# USB2Serial_CH340G_v1_2.net
KiCad netlist of a schematic drawn in EAGLE
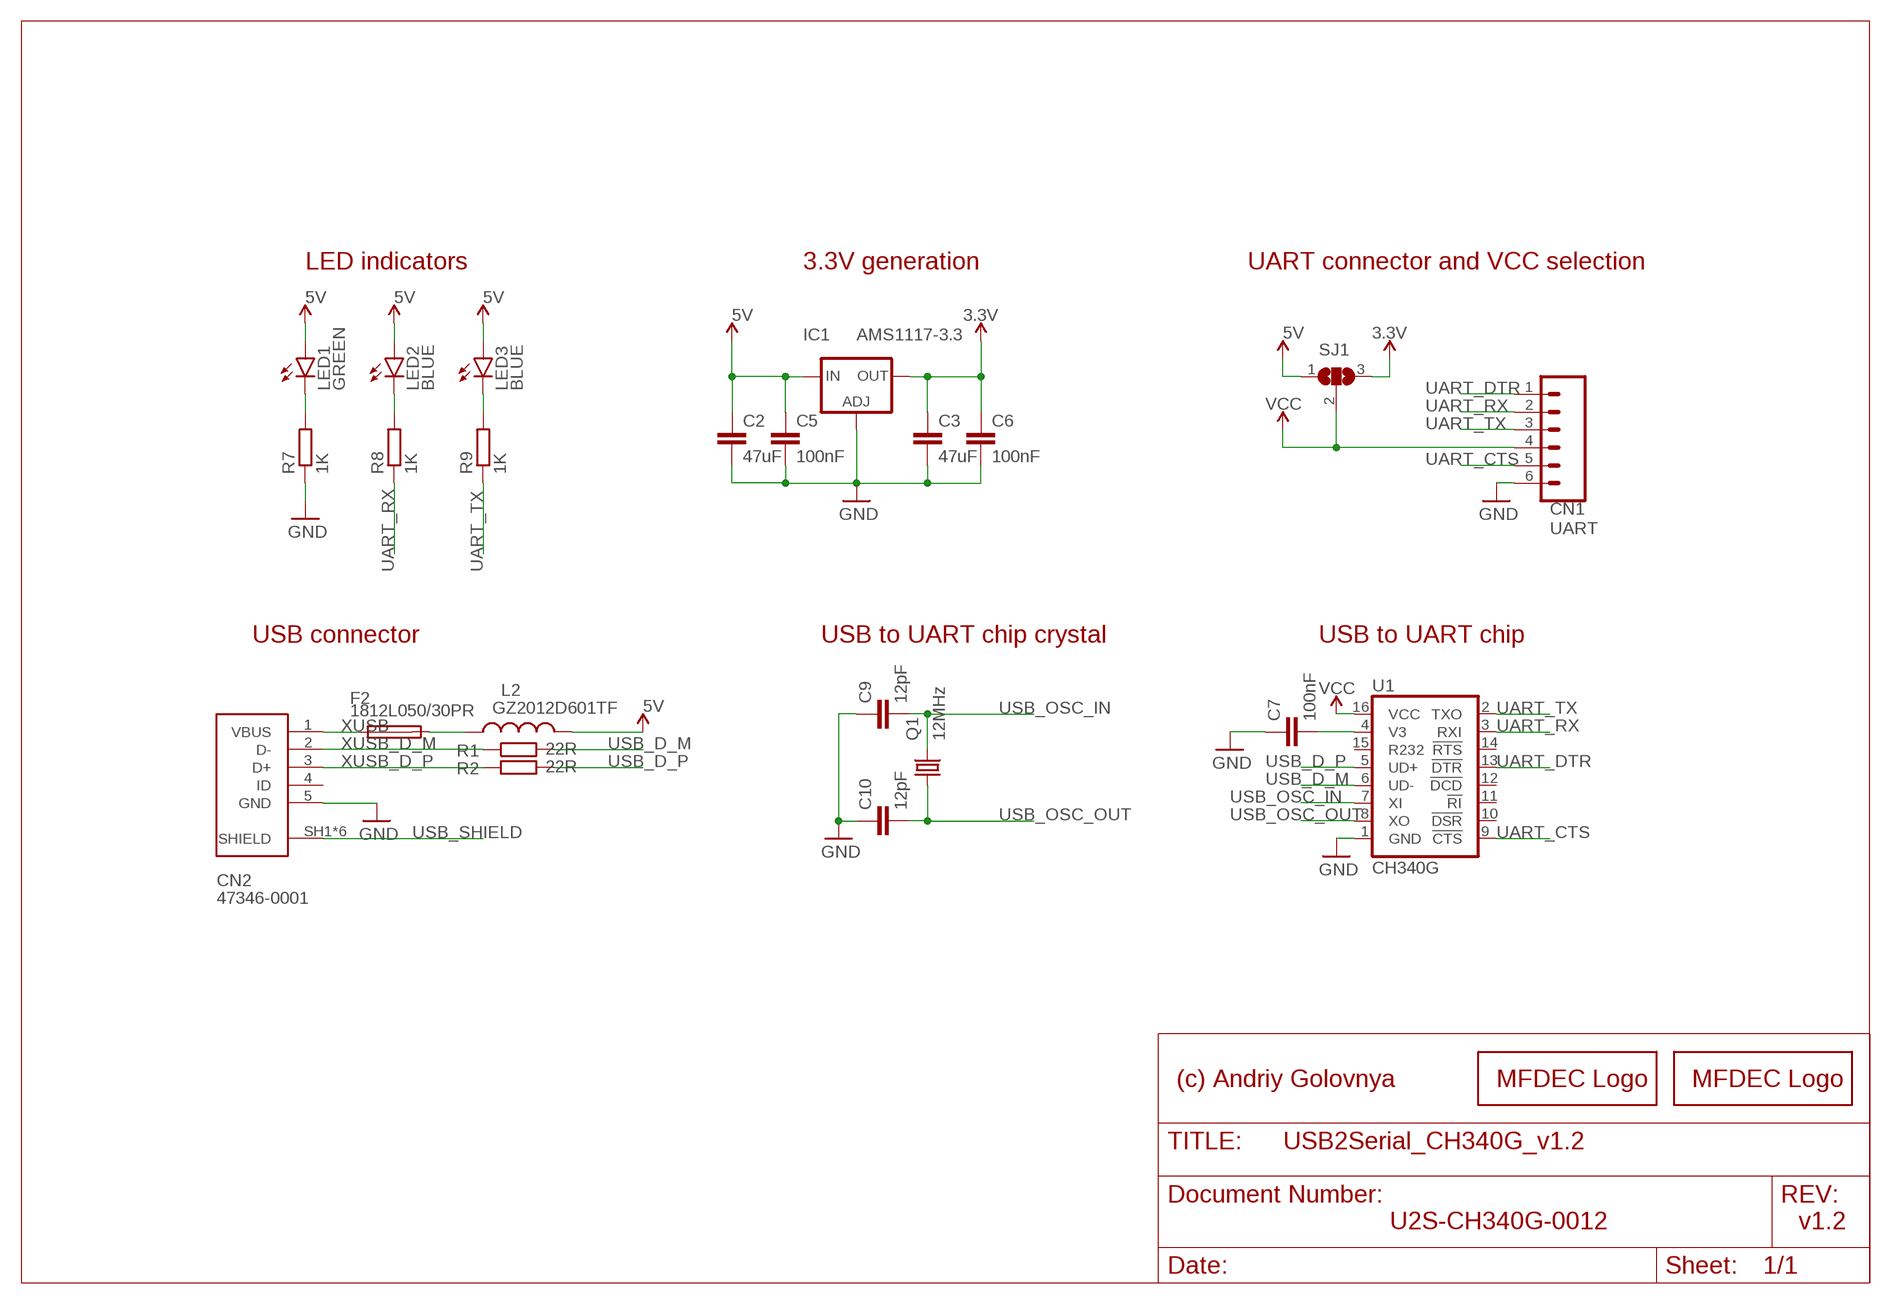
[diagram p0: schematic, sheet 1]

(export (version "E")
  (design (tool "Eeschema 10.0.6"))
  (components
    (comp (ref "C2")
      (value "47uF")
      (footprint "eagle-import:C0805")
      (libsource (lib "eagle-import") (part "C-EUC0805"))
    )
    (comp (ref "C3")
      (value "47uF")
      (footprint "eagle-import:C0805")
      (libsource (lib "eagle-import") (part "C-EUC0805"))
    )
    (comp (ref "C5")
      (value "100nF")
      (footprint "eagle-import:C0402")
      (libsource (lib "eagle-import") (part "C-EUC0402"))
    )
    (comp (ref "C6")
      (value "100nF")
      (footprint "eagle-import:C0402")
      (libsource (lib "eagle-import") (part "C-EUC0402"))
    )
    (comp (ref "C7")
      (value "100nF")
      (footprint "eagle-import:C0402")
      (libsource (lib "eagle-import") (part "C-EUC0402"))
    )
    (comp (ref "C9")
      (value "12pF")
      (footprint "eagle-import:C0402")
      (libsource (lib "eagle-import") (part "C-EUC0402"))
    )
    (comp (ref "C10")
      (value "12pF")
      (footprint "eagle-import:C0402")
      (libsource (lib "eagle-import") (part "C-EUC0402"))
    )
    (comp (ref "CN1")
      (value "UART")
      (footprint "eagle-import:1X06_LOCK")
      (libsource (lib "eagle-import") (part "CONN_06LOCK"))
    )
    (comp (ref "CN2")
      (value "47346-0001")
      (footprint "eagle-import:MOLEX_47346-0001")
      (fields (field (name "MANUFACTURER") "Molex"))
      (libsource (lib "eagle-import") (part "47346-0001"))
    )
    (comp (ref "F2")
      (value "1812L050/30PR")
      (footprint "eagle-import:MF-SMDF050")
      (libsource (lib "eagle-import") (part "MF-SMDF050"))
    )
    (comp (ref "IC1")
      (value "AMS1117-3.3")
      (footprint "eagle-import:SOT223")
      (libsource (lib "eagle-import") (part "LD117A?S33TR"))
    )
    (comp (ref "L2")
      (value "GZ2012D601TF")
      (footprint "eagle-import:WE-CBA_0805(W=4)")
      (libsource (lib "eagle-import") (part "WE-CBA_0805_HC_782853102"))
    )
    (comp (ref "LED1")
      (value "GREEN")
      (footprint "eagle-import:SML0603")
      (libsource (lib "eagle-import") (part "LEDSML0603"))
    )
    (comp (ref "LED2")
      (value "BLUE")
      (footprint "eagle-import:SML0603")
      (libsource (lib "eagle-import") (part "LEDSML0603"))
    )
    (comp (ref "LED3")
      (value "BLUE")
      (footprint "eagle-import:SML0603")
      (libsource (lib "eagle-import") (part "LEDSML0603"))
    )
    (comp (ref "LOGO1")
      (value "MFDECLOGO_L_20MM")
      (footprint "eagle-import:MFDEC_L_20MM")
      (libsource (lib "eagle-import") (part "MFDECLOGO_L_20MM"))
    )
    (comp (ref "LOGO2")
      (value "MFDECLOGO_SQ_10MM")
      (footprint "eagle-import:MFDEC_SQ_10MM")
      (libsource (lib "eagle-import") (part "MFDECLOGO_SQ_10MM"))
    )
    (comp (ref "Q1")
      (value "12MHz")
      (footprint "eagle-import:3.2X2.5_KX-7")
      (libsource (lib "eagle-import") (part "KX-7"))
    )
    (comp (ref "R1")
      (value "22R")
      (footprint "eagle-import:R0402")
      (libsource (lib "eagle-import") (part "R-EU_R0402"))
    )
    (comp (ref "R2")
      (value "22R")
      (footprint "eagle-import:R0402")
      (libsource (lib "eagle-import") (part "R-EU_R0402"))
    )
    (comp (ref "R7")
      (value "1K")
      (footprint "eagle-import:R0402")
      (libsource (lib "eagle-import") (part "R-EU_R0402"))
    )
    (comp (ref "R8")
      (value "1K")
      (footprint "eagle-import:R0402")
      (libsource (lib "eagle-import") (part "R-EU_R0402"))
    )
    (comp (ref "R9")
      (value "1K")
      (footprint "eagle-import:R0402")
      (libsource (lib "eagle-import") (part "R-EU_R0402"))
    )
    (comp (ref "SJ1")
      (value "SJ2FI")
      (footprint "eagle-import:SJ_2FI")
      (libsource (lib "eagle-import") (part "SJ2FI"))
    )
    (comp (ref "U1")
      (value "CH340G")
      (footprint "eagle-import:SO016")
      (libsource (lib "eagle-import") (part "CH340GSMD"))
    )
  )
  (nets
    (net (code "1") (name "/UART_CTS") (class "Default")
      (node (ref "CN1") (pin "5") (pinfunction "5_5") (pintype "passive"))
      (node (ref "U1") (pin "9") (pinfunction "~{CTS}_9") (pintype "bidirectional"))
    )
    (net (code "2") (name "/UART_DTR") (class "Default")
      (node (ref "CN1") (pin "1") (pinfunction "1_1") (pintype "passive"))
      (node (ref "U1") (pin "13") (pinfunction "~{DTR}_13") (pintype "bidirectional"))
    )
    (net (code "3") (name "/UART_RX") (class "Default")
      (node (ref "CN1") (pin "2") (pinfunction "2_2") (pintype "passive"))
      (node (ref "R8") (pin "1") (pinfunction "1_1") (pintype "passive"))
      (node (ref "U1") (pin "3") (pinfunction "RXI_3") (pintype "bidirectional"))
    )
    (net (code "4") (name "/UART_TX") (class "Default")
      (node (ref "CN1") (pin "3") (pinfunction "3_3") (pintype "passive"))
      (node (ref "R9") (pin "1") (pinfunction "1_1") (pintype "passive"))
      (node (ref "U1") (pin "2") (pinfunction "TXO_2") (pintype "bidirectional"))
    )
    (net (code "5") (name "/USB_D_M") (class "Default")
      (node (ref "R1") (pin "2") (pinfunction "2_2") (pintype "passive"))
      (node (ref "U1") (pin "6") (pinfunction "UD-_6") (pintype "bidirectional"))
    )
    (net (code "6") (name "/USB_D_P") (class "Default")
      (node (ref "R2") (pin "2") (pinfunction "2_2") (pintype "passive"))
      (node (ref "U1") (pin "5") (pinfunction "UD+_5") (pintype "bidirectional"))
    )
    (net (code "7") (name "/USB_OSC_IN") (class "Default")
      (node (ref "C9") (pin "2") (pinfunction "2_2") (pintype "passive"))
      (node (ref "Q1") (pin "3") (pinfunction "2_3") (pintype "passive"))
      (node (ref "U1") (pin "7") (pinfunction "XI_7") (pintype "bidirectional"))
    )
    (net (code "8") (name "/USB_OSC_OUT") (class "Default")
      (node (ref "C10") (pin "2") (pinfunction "2_2") (pintype "passive"))
      (node (ref "Q1") (pin "1") (pinfunction "1_1") (pintype "passive"))
      (node (ref "U1") (pin "8") (pinfunction "XO_8") (pintype "bidirectional"))
    )
    (net (code "9") (name "/USB_SHIELD") (class "Default")
      (node (ref "CN2") (pin "SH1") (pinfunction "SHIELD_SH1") (pintype "passive"))
      (node (ref "CN2") (pin "SH2") (pinfunction "SHIELD_SH2") (pintype "passive"))
      (node (ref "CN2") (pin "SH3") (pinfunction "SHIELD_SH3") (pintype "passive"))
      (node (ref "CN2") (pin "SH4") (pinfunction "SHIELD_SH4") (pintype "passive"))
      (node (ref "CN2") (pin "SH5") (pinfunction "SHIELD_SH5") (pintype "passive"))
      (node (ref "CN2") (pin "SH6") (pinfunction "SHIELD_SH6") (pintype "passive"))
    )
    (net (code "10") (name "/XUSB") (class "Default")
      (node (ref "CN2") (pin "1") (pinfunction "VBUS_1") (pintype "power_in"))
      (node (ref "F2") (pin "1") (pinfunction "1_1") (pintype "passive"))
    )
    (net (code "11") (name "/XUSB_D_M") (class "Default")
      (node (ref "CN2") (pin "2") (pinfunction "D-_2") (pintype "bidirectional"))
      (node (ref "R1") (pin "1") (pinfunction "1_1") (pintype "passive"))
    )
    (net (code "12") (name "/XUSB_D_P") (class "Default")
      (node (ref "CN2") (pin "3") (pinfunction "D+_3") (pintype "bidirectional"))
      (node (ref "R2") (pin "1") (pinfunction "1_1") (pintype "passive"))
    )
    (net (code "13") (name "3.3V") (class "Default")
      (node (ref "C3") (pin "1") (pinfunction "1_1") (pintype "passive"))
      (node (ref "C6") (pin "1") (pinfunction "1_1") (pintype "passive"))
      (node (ref "IC1") (pin "4") (pinfunction "OUT_4") (pintype "passive"))
      (node (ref "SJ1") (pin "3") (pinfunction "3_3") (pintype "passive"))
    )
    (net (code "14") (name "5V") (class "Default")
      (node (ref "C2") (pin "1") (pinfunction "1_1") (pintype "passive"))
      (node (ref "C5") (pin "1") (pinfunction "1_1") (pintype "passive"))
      (node (ref "IC1") (pin "3") (pinfunction "IN_3") (pintype "input"))
      (node (ref "L2") (pin "2") (pinfunction "2_2") (pintype "passive"))
      (node (ref "LED1") (pin "A") (pinfunction "A_A") (pintype "passive"))
      (node (ref "LED2") (pin "A") (pinfunction "A_A") (pintype "passive"))
      (node (ref "LED3") (pin "A") (pinfunction "A_A") (pintype "passive"))
      (node (ref "SJ1") (pin "1") (pinfunction "1_1") (pintype "passive"))
    )
    (net (code "15") (name "GND") (class "Default")
      (node (ref "C10") (pin "1") (pinfunction "1_1") (pintype "passive"))
      (node (ref "C2") (pin "2") (pinfunction "2_2") (pintype "passive"))
      (node (ref "C3") (pin "2") (pinfunction "2_2") (pintype "passive"))
      (node (ref "C5") (pin "2") (pinfunction "2_2") (pintype "passive"))
      (node (ref "C6") (pin "2") (pinfunction "2_2") (pintype "passive"))
      (node (ref "C7") (pin "1") (pinfunction "1_1") (pintype "passive"))
      (node (ref "C9") (pin "1") (pinfunction "1_1") (pintype "passive"))
      (node (ref "CN1") (pin "6") (pinfunction "6_6") (pintype "passive"))
      (node (ref "CN2") (pin "5") (pinfunction "GND_5") (pintype "power_in"))
      (node (ref "IC1") (pin "1") (pinfunction "ADJ_1") (pintype "input"))
      (node (ref "R7") (pin "1") (pinfunction "1_1") (pintype "passive"))
      (node (ref "U1") (pin "1") (pinfunction "GND_1") (pintype "bidirectional"))
    )
    (net (code "16") (name "Net-(F2-Pad2)") (class "Default")
      (node (ref "F2") (pin "2") (pinfunction "2_2") (pintype "passive"))
      (node (ref "L2") (pin "1") (pinfunction "1_1") (pintype "passive"))
    )
    (net (code "17") (name "Net-(LED1-PadC)") (class "Default")
      (node (ref "LED1") (pin "C") (pinfunction "C_C") (pintype "passive"))
      (node (ref "R7") (pin "2") (pinfunction "2_2") (pintype "passive"))
    )
    (net (code "18") (name "Net-(LED2-PadC)") (class "Default")
      (node (ref "LED2") (pin "C") (pinfunction "C_C") (pintype "passive"))
      (node (ref "R8") (pin "2") (pinfunction "2_2") (pintype "passive"))
    )
    (net (code "19") (name "Net-(LED3-PadC)") (class "Default")
      (node (ref "LED3") (pin "C") (pinfunction "C_C") (pintype "passive"))
      (node (ref "R9") (pin "2") (pinfunction "2_2") (pintype "passive"))
    )
    (net (code "20") (name "Net-(U1-V3)") (class "Default")
      (node (ref "C7") (pin "2") (pinfunction "2_2") (pintype "passive"))
      (node (ref "U1") (pin "4") (pinfunction "V3_4") (pintype "bidirectional"))
    )
    (net (code "21") (name "VCC") (class "Default")
      (node (ref "CN1") (pin "4") (pinfunction "4_4") (pintype "passive"))
      (node (ref "SJ1") (pin "2") (pinfunction "2_2") (pintype "passive"))
      (node (ref "U1") (pin "16") (pinfunction "VCC_16") (pintype "bidirectional"))
    )
    (net (code "22") (name "unconnected-(CN2-ID-Pad4)") (class "Default")
      (node (ref "CN2") (pin "4") (pinfunction "ID_4") (pintype "passive"))
    )
    (net (code "23") (name "unconnected-(U1-R232-Pad15)") (class "Default")
      (node (ref "U1") (pin "15") (pinfunction "R232_15") (pintype "bidirectional"))
    )
    (net (code "24") (name "unconnected-(U1-~{DCD}-Pad12)") (class "Default")
      (node (ref "U1") (pin "12") (pinfunction "~{DCD}_12") (pintype "bidirectional"))
    )
    (net (code "25") (name "unconnected-(U1-~{DSR}-Pad10)") (class "Default")
      (node (ref "U1") (pin "10") (pinfunction "~{DSR}_10") (pintype "bidirectional"))
    )
    (net (code "26") (name "unconnected-(U1-~{RI}-Pad11)") (class "Default")
      (node (ref "U1") (pin "11") (pinfunction "~{RI}_11") (pintype "bidirectional"))
    )
    (net (code "27") (name "unconnected-(U1-~{RTS}-Pad14)") (class "Default")
      (node (ref "U1") (pin "14") (pinfunction "~{RTS}_14") (pintype "bidirectional"))
    )
  )
)
